# PLL.net
KiCad netlist of a schematic drawn in Altium Designer
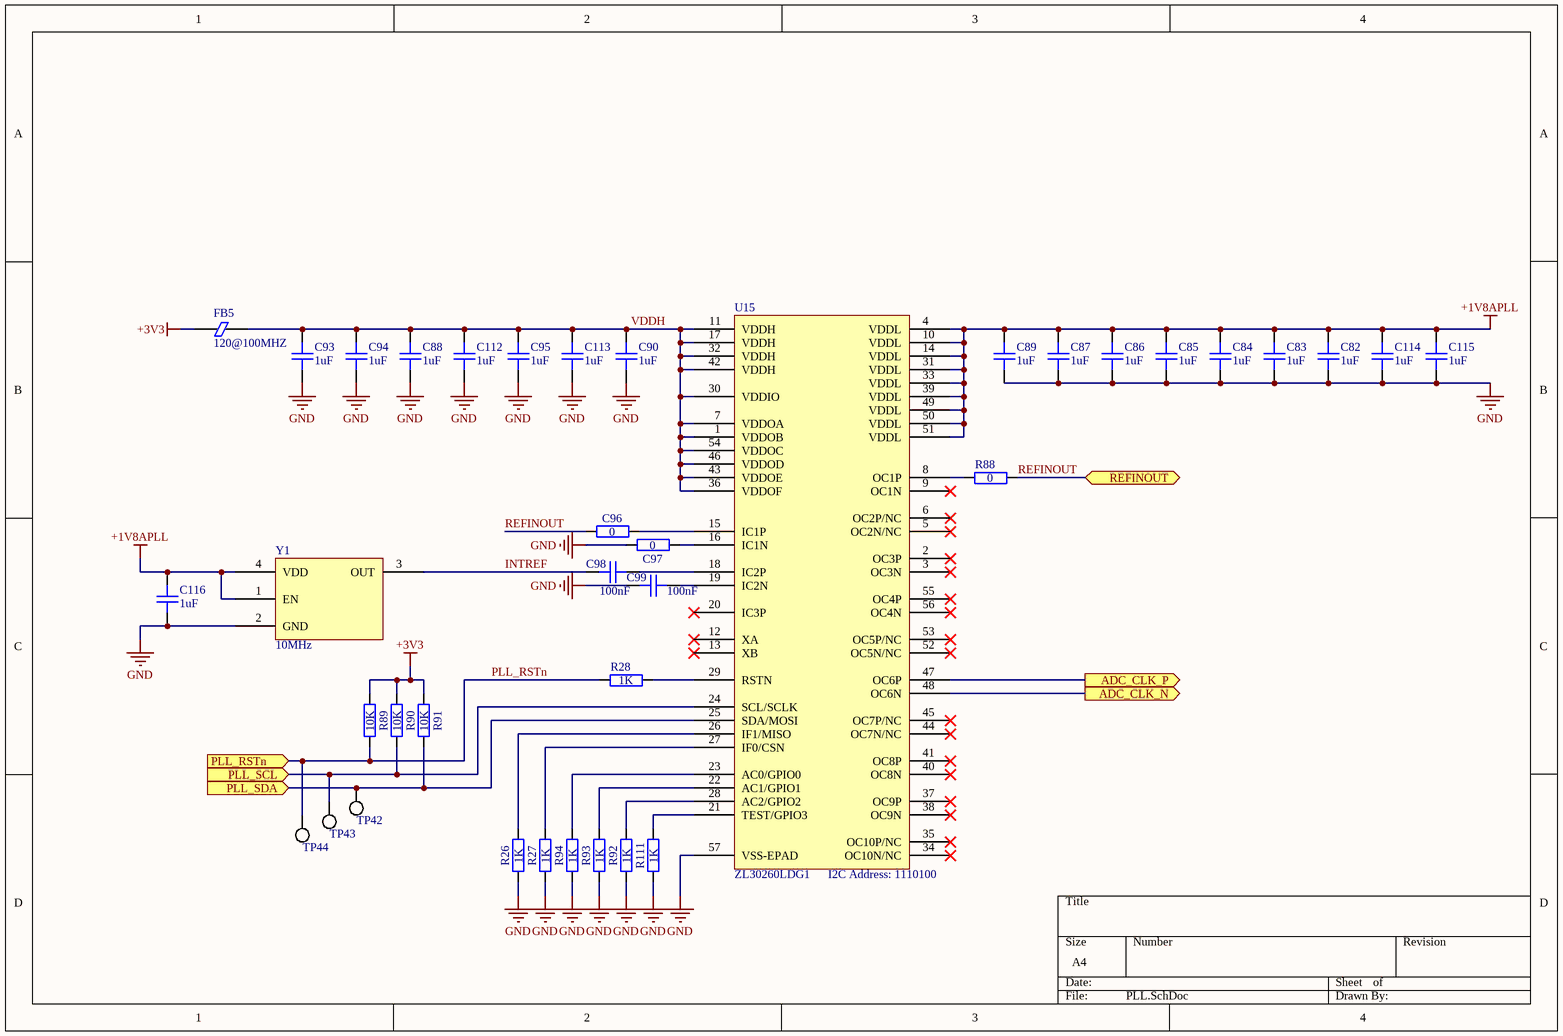
[diagram p0: PLL.SchDoc]

(export (version "E")
  (design (tool "Eeschema 10.0.6"))
  (components
    (comp (ref "C82")
      (value "1uF")
      (footprint "GEN_C_0402")
      (libsource (lib "DSO") (part "CAP 1uF 25V X5R 0402"))
    )
    (comp (ref "C83")
      (value "1uF")
      (footprint "GEN_C_0402")
      (libsource (lib "DSO") (part "CAP 1uF 25V X5R 0402"))
    )
    (comp (ref "C84")
      (value "1uF")
      (footprint "GEN_C_0402")
      (libsource (lib "DSO") (part "CAP 1uF 25V X5R 0402"))
    )
    (comp (ref "C85")
      (value "1uF")
      (footprint "GEN_C_0402")
      (libsource (lib "DSO") (part "CAP 1uF 25V X5R 0402"))
    )
    (comp (ref "C86")
      (value "1uF")
      (footprint "GEN_C_0402")
      (libsource (lib "DSO") (part "CAP 1uF 25V X5R 0402"))
    )
    (comp (ref "C87")
      (value "1uF")
      (footprint "GEN_C_0402")
      (libsource (lib "DSO") (part "CAP 1uF 25V X5R 0402"))
    )
    (comp (ref "C88")
      (value "1uF")
      (footprint "GEN_C_0402")
      (libsource (lib "DSO") (part "CAP 1uF 25V X5R 0402"))
    )
    (comp (ref "C89")
      (value "1uF")
      (footprint "GEN_C_0402")
      (libsource (lib "DSO") (part "CAP 1uF 25V X5R 0402"))
    )
    (comp (ref "C90")
      (value "1uF")
      (footprint "GEN_C_0402")
      (libsource (lib "DSO") (part "CAP 1uF 25V X5R 0402"))
    )
    (comp (ref "C93")
      (value "1uF")
      (footprint "GEN_C_0402")
      (libsource (lib "DSO") (part "CAP 1uF 25V X5R 0402"))
    )
    (comp (ref "C94")
      (value "1uF")
      (footprint "GEN_C_0402")
      (libsource (lib "DSO") (part "CAP 1uF 25V X5R 0402"))
    )
    (comp (ref "C95")
      (value "1uF")
      (footprint "GEN_C_0402")
      (libsource (lib "DSO") (part "CAP 1uF 25V X5R 0402"))
    )
    (comp (ref "C96")
      (value "0")
      (footprint "GEN_R_0402")
      (fields
        (field (name "MANUFACTURER") "Yageo")
        (field (name "MANUFACTURER PART NUMBER") "RC0402JR-070RL")
      )
      (libsource (lib "") (part "RES 0 OHM 1/16W 0402_1"))
    )
    (comp (ref "C97")
      (value "0")
      (footprint "GEN_R_0402")
      (fields
        (field (name "MANUFACTURER") "Yageo")
        (field (name "MANUFACTURER PART NUMBER") "RC0402JR-070RL")
      )
      (libsource (lib "") (part "RES 0 OHM 1/16W 0402_1"))
    )
    (comp (ref "C98")
      (value "100nF")
      (footprint "GEN_C_0402")
      (libsource (lib "DSO") (part "CAP 100nF 16V X7R 0402"))
    )
    (comp (ref "C99")
      (value "100nF")
      (footprint "GEN_C_0402")
      (libsource (lib "DSO") (part "CAP 100nF 16V X7R 0402"))
    )
    (comp (ref "C112")
      (value "1uF")
      (footprint "GEN_C_0402")
      (libsource (lib "DSO") (part "CAP 1uF 25V X5R 0402"))
    )
    (comp (ref "C113")
      (value "1uF")
      (footprint "GEN_C_0402")
      (libsource (lib "DSO") (part "CAP 1uF 25V X5R 0402"))
    )
    (comp (ref "C114")
      (value "1uF")
      (footprint "GEN_C_0402")
      (libsource (lib "DSO") (part "CAP 1uF 25V X5R 0402"))
    )
    (comp (ref "C115")
      (value "1uF")
      (footprint "GEN_C_0402")
      (libsource (lib "DSO") (part "CAP 1uF 25V X5R 0402"))
    )
    (comp (ref "C116")
      (value "1uF")
      (footprint "GEN_C_0402")
      (libsource (lib "DSO") (part "CAP 1uF 25V X5R 0402"))
    )
    (comp (ref "FB5")
      (value "120@100MHZ")
      (footprint "GEN_R_0402")
      (libsource (lib "DSO") (part "FERRITE BEAD 120 OHM 0402"))
    )
    (comp (ref "R26")
      (value "1K")
      (footprint "GEN_R_0402")
      (fields
        (field (name "TOLERANCE") "1%")
        (field (name "MANUFACTURER") "Yageo")
        (field (name "HOUSE PART NUMBER") "R-1K-0402-1%-001")
      )
      (libsource (lib "DSO") (part "RES 1K OHM 1% 1/10W 0402"))
    )
    (comp (ref "R27")
      (value "1K")
      (footprint "GEN_R_0402")
      (fields
        (field (name "TOLERANCE") "1%")
        (field (name "MANUFACTURER") "Yageo")
        (field (name "HOUSE PART NUMBER") "R-1K-0402-1%-001")
      )
      (libsource (lib "DSO") (part "RES 1K OHM 1% 1/10W 0402"))
    )
    (comp (ref "R28")
      (value "1K")
      (footprint "GEN_R_0402")
      (fields
        (field (name "TOLERANCE") "1%")
        (field (name "MANUFACTURER") "Yageo")
        (field (name "HOUSE PART NUMBER") "R-1K-0402-1%-001")
      )
      (libsource (lib "") (part "RES 1K OHM 1% 1/10W 0402_1"))
    )
    (comp (ref "R88")
      (value "0")
      (footprint "GEN_R_0402")
      (libsource (lib "DSO") (part "RES 0 OHM 1/16W 0402"))
    )
    (comp (ref "R89")
      (value "10K")
      (footprint "GEN_R_0402")
      (fields (field (name "TOLERANCE") "1%"))
      (libsource (lib "DSO") (part "RES 10K OHM 1% 1/10W 0402"))
    )
    (comp (ref "R90")
      (value "10K")
      (footprint "GEN_R_0402")
      (fields (field (name "TOLERANCE") "1%"))
      (libsource (lib "DSO") (part "RES 10K OHM 1% 1/10W 0402"))
    )
    (comp (ref "R91")
      (value "10K")
      (footprint "GEN_R_0402")
      (fields (field (name "TOLERANCE") "1%"))
      (libsource (lib "DSO") (part "RES 10K OHM 1% 1/10W 0402"))
    )
    (comp (ref "R92")
      (value "1K")
      (footprint "GEN_R_0402")
      (fields
        (field (name "TOLERANCE") "1%")
        (field (name "MANUFACTURER") "Yageo")
        (field (name "HOUSE PART NUMBER") "R-1K-0402-1%-001")
      )
      (libsource (lib "DSO") (part "RES 1K OHM 1% 1/10W 0402"))
    )
    (comp (ref "R93")
      (value "1K")
      (footprint "GEN_R_0402")
      (fields
        (field (name "TOLERANCE") "1%")
        (field (name "MANUFACTURER") "Yageo")
        (field (name "HOUSE PART NUMBER") "R-1K-0402-1%-001")
      )
      (libsource (lib "DSO") (part "RES 1K OHM 1% 1/10W 0402"))
    )
    (comp (ref "R94")
      (value "1K")
      (footprint "GEN_R_0402")
      (fields
        (field (name "TOLERANCE") "1%")
        (field (name "MANUFACTURER") "Yageo")
        (field (name "HOUSE PART NUMBER") "R-1K-0402-1%-001")
      )
      (libsource (lib "DSO") (part "RES 1K OHM 1% 1/10W 0402"))
    )
    (comp (ref "R111")
      (value "1K")
      (footprint "GEN_R_0402")
      (fields
        (field (name "TOLERANCE") "1%")
        (field (name "MANUFACTURER") "Yageo")
        (field (name "HOUSE PART NUMBER") "R-1K-0402-1%-001")
      )
      (libsource (lib "DSO") (part "RES 1K OHM 1% 1/10W 0402"))
    )
    (comp (ref "TP42") (value "PCB") (footprint "GEN_TP_PCB") (libsource (lib "DSO") (part "TP PCB 1mm")))
    (comp (ref "TP43") (value "PCB") (footprint "GEN_TP_PCB") (libsource (lib "DSO") (part "TP PCB 1mm")))
    (comp (ref "TP44") (value "PCB") (footprint "GEN_TP_PCB") (libsource (lib "DSO") (part "TP PCB 1mm")))
    (comp (ref "U15")
      (value "ZL30260LDG1")
      (footprint "MC_QFN56_ZL30260")
      (fields (field (name "MANUFACTURER") "Microchip"))
      (libsource (lib "DSO") (part "IC CLK GEN ZL30260LDG1"))
    )
    (comp (ref "Y1")
      (value "10MHz")
      (footprint "ECS_TXO-3225")
      (libsource (lib "DSO") (part "OSC 10MHz ECS-TXO-3225MV"))
    )
  )
  (nets
    (net (code "1") (name "+1V8APLL") (class "Default")
      (node (ref "C114") (pin "1") (pinfunction "1_1") (pintype "passive"))
      (node (ref "C115") (pin "1") (pinfunction "1_1") (pintype "passive"))
      (node (ref "C116") (pin "1") (pinfunction "1_1") (pintype "passive"))
      (node (ref "C82") (pin "1") (pinfunction "1_1") (pintype "passive"))
      (node (ref "C83") (pin "1") (pinfunction "1_1") (pintype "passive"))
      (node (ref "C84") (pin "1") (pinfunction "1_1") (pintype "passive"))
      (node (ref "C85") (pin "1") (pinfunction "1_1") (pintype "passive"))
      (node (ref "C86") (pin "1") (pinfunction "1_1") (pintype "passive"))
      (node (ref "C87") (pin "1") (pinfunction "1_1") (pintype "passive"))
      (node (ref "C89") (pin "1") (pinfunction "1_1") (pintype "passive"))
      (node (ref "U15") (pin "10") (pinfunction "VDDL_10") (pintype "passive"))
      (node (ref "U15") (pin "14") (pinfunction "VDDL_14") (pintype "passive"))
      (node (ref "U15") (pin "31") (pinfunction "VDDL_31") (pintype "passive"))
      (node (ref "U15") (pin "33") (pinfunction "VDDL_33") (pintype "passive"))
      (node (ref "U15") (pin "39") (pinfunction "VDDL_39") (pintype "passive"))
      (node (ref "U15") (pin "4") (pinfunction "VDDL_4") (pintype "passive"))
      (node (ref "U15") (pin "49") (pinfunction "VDDL_49") (pintype "passive"))
      (node (ref "U15") (pin "50") (pinfunction "VDDL_50") (pintype "passive"))
      (node (ref "U15") (pin "51") (pinfunction "VDDL_51") (pintype "passive"))
      (node (ref "Y1") (pin "1") (pinfunction "EN_1") (pintype "passive"))
      (node (ref "Y1") (pin "4") (pinfunction "VDD_4") (pintype "power_in"))
    )
    (net (code "2") (name "+3V3") (class "Default")
      (node (ref "FB5") (pin "1") (pinfunction "1_1") (pintype "passive"))
      (node (ref "R89") (pin "2") (pinfunction "2_2") (pintype "passive"))
      (node (ref "R90") (pin "2") (pinfunction "2_2") (pintype "passive"))
      (node (ref "R91") (pin "2") (pinfunction "2_2") (pintype "passive"))
    )
    (net (code "3") (name "/ADC_CLK_N") (class "Default")
      (node (ref "U15") (pin "48") (pinfunction "OC6N_48") (pintype "passive"))
    )
    (net (code "4") (name "/ADC_CLK_P") (class "Default")
      (node (ref "U15") (pin "47") (pinfunction "OC6P_47") (pintype "passive"))
    )
    (net (code "5") (name "/INTREF") (class "Default")
      (node (ref "C98") (pin "2") (pinfunction "2_2") (pintype "passive"))
      (node (ref "Y1") (pin "3") (pinfunction "OUT_3") (pintype "passive"))
    )
    (net (code "6") (name "/PLL_RSTn") (class "Default")
      (node (ref "R28") (pin "2") (pinfunction "2_2") (pintype "passive"))
      (node (ref "R89") (pin "1") (pinfunction "1_1") (pintype "passive"))
      (node (ref "TP44") (pin "1") (pinfunction "1_1") (pintype "passive"))
    )
    (net (code "7") (name "/PLL_SCL") (class "Default")
      (node (ref "R90") (pin "1") (pinfunction "1_1") (pintype "passive"))
      (node (ref "TP43") (pin "1") (pinfunction "1_1") (pintype "passive"))
      (node (ref "U15") (pin "24") (pinfunction "SCL/SCLK_24") (pintype "passive"))
    )
    (net (code "8") (name "/PLL_SDA") (class "Default")
      (node (ref "R91") (pin "1") (pinfunction "1_1") (pintype "passive"))
      (node (ref "TP42") (pin "1") (pinfunction "1_1") (pintype "passive"))
      (node (ref "U15") (pin "25") (pinfunction "SDA/MOSI_25") (pintype "passive"))
    )
    (net (code "9") (name "/REFINOUT") (class "Default")
      (node (ref "C96") (pin "2") (pinfunction "2_2") (pintype "passive"))
      (node (ref "R88") (pin "2") (pinfunction "2_2") (pintype "passive"))
    )
    (net (code "10") (name "/VDDH") (class "Default")
      (node (ref "C112") (pin "1") (pinfunction "1_1") (pintype "passive"))
      (node (ref "C113") (pin "1") (pinfunction "1_1") (pintype "passive"))
      (node (ref "C88") (pin "1") (pinfunction "1_1") (pintype "passive"))
      (node (ref "C90") (pin "1") (pinfunction "1_1") (pintype "passive"))
      (node (ref "C93") (pin "1") (pinfunction "1_1") (pintype "passive"))
      (node (ref "C94") (pin "1") (pinfunction "1_1") (pintype "passive"))
      (node (ref "C95") (pin "1") (pinfunction "1_1") (pintype "passive"))
      (node (ref "FB5") (pin "2") (pinfunction "2_2") (pintype "passive"))
      (node (ref "U15") (pin "1") (pinfunction "VDDOB_1") (pintype "passive"))
      (node (ref "U15") (pin "11") (pinfunction "VDDH_11") (pintype "passive"))
      (node (ref "U15") (pin "17") (pinfunction "VDDH_17") (pintype "passive"))
      (node (ref "U15") (pin "30") (pinfunction "VDDIO_30") (pintype "passive"))
      (node (ref "U15") (pin "32") (pinfunction "VDDH_32") (pintype "passive"))
      (node (ref "U15") (pin "36") (pinfunction "VDDOF_36") (pintype "passive"))
      (node (ref "U15") (pin "42") (pinfunction "VDDH_42") (pintype "passive"))
      (node (ref "U15") (pin "43") (pinfunction "VDDOE_43") (pintype "passive"))
      (node (ref "U15") (pin "46") (pinfunction "VDDOD_46") (pintype "passive"))
      (node (ref "U15") (pin "54") (pinfunction "VDDOC_54") (pintype "passive"))
      (node (ref "U15") (pin "7") (pinfunction "VDDOA_7") (pintype "passive"))
    )
    (net (code "11") (name "GND") (class "Default")
      (node (ref "C112") (pin "2") (pinfunction "2_2") (pintype "passive"))
      (node (ref "C113") (pin "2") (pinfunction "2_2") (pintype "passive"))
      (node (ref "C114") (pin "2") (pinfunction "2_2") (pintype "passive"))
      (node (ref "C115") (pin "2") (pinfunction "2_2") (pintype "passive"))
      (node (ref "C116") (pin "2") (pinfunction "2_2") (pintype "passive"))
      (node (ref "C82") (pin "2") (pinfunction "2_2") (pintype "passive"))
      (node (ref "C83") (pin "2") (pinfunction "2_2") (pintype "passive"))
      (node (ref "C84") (pin "2") (pinfunction "2_2") (pintype "passive"))
      (node (ref "C85") (pin "2") (pinfunction "2_2") (pintype "passive"))
      (node (ref "C86") (pin "2") (pinfunction "2_2") (pintype "passive"))
      (node (ref "C87") (pin "2") (pinfunction "2_2") (pintype "passive"))
      (node (ref "C88") (pin "2") (pinfunction "2_2") (pintype "passive"))
      (node (ref "C89") (pin "2") (pinfunction "2_2") (pintype "passive"))
      (node (ref "C90") (pin "2") (pinfunction "2_2") (pintype "passive"))
      (node (ref "C93") (pin "2") (pinfunction "2_2") (pintype "passive"))
      (node (ref "C94") (pin "2") (pinfunction "2_2") (pintype "passive"))
      (node (ref "C95") (pin "2") (pinfunction "2_2") (pintype "passive"))
      (node (ref "C97") (pin "2") (pinfunction "2_2") (pintype "passive"))
      (node (ref "C99") (pin "2") (pinfunction "2_2") (pintype "passive"))
      (node (ref "R111") (pin "1") (pinfunction "1_1") (pintype "passive"))
      (node (ref "R26") (pin "1") (pinfunction "1_1") (pintype "passive"))
      (node (ref "R27") (pin "1") (pinfunction "1_1") (pintype "passive"))
      (node (ref "R92") (pin "1") (pinfunction "1_1") (pintype "passive"))
      (node (ref "R93") (pin "1") (pinfunction "1_1") (pintype "passive"))
      (node (ref "R94") (pin "1") (pinfunction "1_1") (pintype "passive"))
      (node (ref "U15") (pin "57") (pinfunction "VSS-EPAD_57") (pintype "passive"))
      (node (ref "Y1") (pin "2") (pinfunction "GND_2") (pintype "power_in"))
    )
    (net (code "12") (name "Net-(U15-AC0{slash}GPIO0)") (class "Default")
      (node (ref "R94") (pin "2") (pinfunction "2_2") (pintype "passive"))
      (node (ref "U15") (pin "23") (pinfunction "AC0/GPIO0_23") (pintype "passive"))
    )
    (net (code "13") (name "Net-(U15-AC1{slash}GPIO1)") (class "Default")
      (node (ref "R93") (pin "2") (pinfunction "2_2") (pintype "passive"))
      (node (ref "U15") (pin "22") (pinfunction "AC1/GPIO1_22") (pintype "passive"))
    )
    (net (code "14") (name "Net-(U15-AC2{slash}GPIO2)") (class "Default")
      (node (ref "R92") (pin "2") (pinfunction "2_2") (pintype "passive"))
      (node (ref "U15") (pin "28") (pinfunction "AC2/GPIO2_28") (pintype "passive"))
    )
    (net (code "15") (name "Net-(U15-IC1N)") (class "Default")
      (node (ref "C97") (pin "1") (pinfunction "1_1") (pintype "passive"))
      (node (ref "U15") (pin "16") (pinfunction "IC1N_16") (pintype "passive"))
    )
    (net (code "16") (name "Net-(U15-IC1P)") (class "Default")
      (node (ref "C96") (pin "1") (pinfunction "1_1") (pintype "passive"))
      (node (ref "U15") (pin "15") (pinfunction "IC1P_15") (pintype "passive"))
    )
    (net (code "17") (name "Net-(U15-IC2N)") (class "Default")
      (node (ref "C99") (pin "1") (pinfunction "1_1") (pintype "passive"))
      (node (ref "U15") (pin "19") (pinfunction "IC2N_19") (pintype "passive"))
    )
    (net (code "18") (name "Net-(U15-IC2P)") (class "Default")
      (node (ref "C98") (pin "1") (pinfunction "1_1") (pintype "passive"))
      (node (ref "U15") (pin "18") (pinfunction "IC2P_18") (pintype "passive"))
    )
    (net (code "19") (name "Net-(U15-IF0{slash}CSN)") (class "Default")
      (node (ref "R27") (pin "2") (pinfunction "2_2") (pintype "passive"))
      (node (ref "U15") (pin "27") (pinfunction "IF0/CSN_27") (pintype "passive"))
    )
    (net (code "20") (name "Net-(U15-IF1{slash}MISO)") (class "Default")
      (node (ref "R26") (pin "2") (pinfunction "2_2") (pintype "passive"))
      (node (ref "U15") (pin "26") (pinfunction "IF1/MISO_26") (pintype "passive"))
    )
    (net (code "21") (name "Net-(U15-OC1P)") (class "Default")
      (node (ref "R88") (pin "1") (pinfunction "1_1") (pintype "passive"))
      (node (ref "U15") (pin "8") (pinfunction "OC1P_8") (pintype "passive"))
    )
    (net (code "22") (name "Net-(U15-RSTN)") (class "Default")
      (node (ref "R28") (pin "1") (pinfunction "1_1") (pintype "passive"))
      (node (ref "U15") (pin "29") (pinfunction "RSTN_29") (pintype "passive"))
    )
    (net (code "23") (name "Net-(U15-TEST{slash}GPIO3)") (class "Default")
      (node (ref "R111") (pin "2") (pinfunction "2_2") (pintype "passive"))
      (node (ref "U15") (pin "21") (pinfunction "TEST/GPIO3_21") (pintype "passive"))
    )
    (net (code "24") (name "unconnected-(U15-IC3P-Pad20)") (class "Default")
      (node (ref "U15") (pin "20") (pinfunction "IC3P_20") (pintype "passive+no_connect"))
    )
    (net (code "25") (name "unconnected-(U15-OC1N-Pad9)") (class "Default")
      (node (ref "U15") (pin "9") (pinfunction "OC1N_9") (pintype "passive+no_connect"))
    )
    (net (code "26") (name "unconnected-(U15-OC2N{slash}NC-Pad5)") (class "Default")
      (node (ref "U15") (pin "5") (pinfunction "OC2N/NC_5") (pintype "passive+no_connect"))
    )
    (net (code "27") (name "unconnected-(U15-OC2P{slash}NC-Pad6)") (class "Default")
      (node (ref "U15") (pin "6") (pinfunction "OC2P/NC_6") (pintype "passive+no_connect"))
    )
    (net (code "28") (name "unconnected-(U15-OC3N-Pad3)") (class "Default")
      (node (ref "U15") (pin "3") (pinfunction "OC3N_3") (pintype "passive+no_connect"))
    )
    (net (code "29") (name "unconnected-(U15-OC3P-Pad2)") (class "Default")
      (node (ref "U15") (pin "2") (pinfunction "OC3P_2") (pintype "passive+no_connect"))
    )
    (net (code "30") (name "unconnected-(U15-OC4N-Pad56)") (class "Default")
      (node (ref "U15") (pin "56") (pinfunction "OC4N_56") (pintype "passive+no_connect"))
    )
    (net (code "31") (name "unconnected-(U15-OC4P-Pad55)") (class "Default")
      (node (ref "U15") (pin "55") (pinfunction "OC4P_55") (pintype "passive+no_connect"))
    )
    (net (code "32") (name "unconnected-(U15-OC5N{slash}NC-Pad52)") (class "Default")
      (node (ref "U15") (pin "52") (pinfunction "OC5N/NC_52") (pintype "passive+no_connect"))
    )
    (net (code "33") (name "unconnected-(U15-OC5P{slash}NC-Pad53)") (class "Default")
      (node (ref "U15") (pin "53") (pinfunction "OC5P/NC_53") (pintype "passive+no_connect"))
    )
    (net (code "34") (name "unconnected-(U15-OC7N{slash}NC-Pad44)") (class "Default")
      (node (ref "U15") (pin "44") (pinfunction "OC7N/NC_44") (pintype "passive+no_connect"))
    )
    (net (code "35") (name "unconnected-(U15-OC7P{slash}NC-Pad45)") (class "Default")
      (node (ref "U15") (pin "45") (pinfunction "OC7P/NC_45") (pintype "passive+no_connect"))
    )
    (net (code "36") (name "unconnected-(U15-OC8N-Pad40)") (class "Default")
      (node (ref "U15") (pin "40") (pinfunction "OC8N_40") (pintype "passive+no_connect"))
    )
    (net (code "37") (name "unconnected-(U15-OC8P-Pad41)") (class "Default")
      (node (ref "U15") (pin "41") (pinfunction "OC8P_41") (pintype "passive+no_connect"))
    )
    (net (code "38") (name "unconnected-(U15-OC9N-Pad38)") (class "Default")
      (node (ref "U15") (pin "38") (pinfunction "OC9N_38") (pintype "passive+no_connect"))
    )
    (net (code "39") (name "unconnected-(U15-OC9P-Pad37)") (class "Default")
      (node (ref "U15") (pin "37") (pinfunction "OC9P_37") (pintype "passive+no_connect"))
    )
    (net (code "40") (name "unconnected-(U15-OC10N{slash}NC-Pad34)") (class "Default")
      (node (ref "U15") (pin "34") (pinfunction "OC10N/NC_34") (pintype "passive+no_connect"))
    )
    (net (code "41") (name "unconnected-(U15-OC10P{slash}NC-Pad35)") (class "Default")
      (node (ref "U15") (pin "35") (pinfunction "OC10P/NC_35") (pintype "passive+no_connect"))
    )
    (net (code "42") (name "unconnected-(U15-XA-Pad12)") (class "Default")
      (node (ref "U15") (pin "12") (pinfunction "XA_12") (pintype "passive+no_connect"))
    )
    (net (code "43") (name "unconnected-(U15-XB-Pad13)") (class "Default")
      (node (ref "U15") (pin "13") (pinfunction "XB_13") (pintype "passive+no_connect"))
    )
  )
)
